# Angular_Position_Feedback.net
KiCad netlist of a schematic drawn in Altium Designer
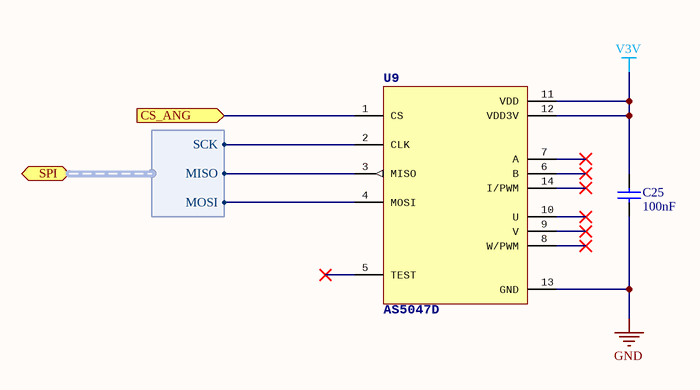
[diagram p0: Angular_Position_Feedback.SchDoc]

(export (version "E")
  (design (tool "Eeschema 10.0.6"))
  (components
    (comp (ref "C25")
      (value "100nF")
      (footprint "CAPC1608X06N (0603)")
      (description "Capacitor (Semiconductor SIM Model)")
      (fields (field (name "Comment") "Cap Semi") (field (name "PUBLISHER") "Altium Limited"))
      (libsource (lib "miStepper_SchematicLib") (part "Cap Semi"))
    )
    (comp (ref "U9")
      (value "AS5047D")
      (footprint "TSSOP14")
      (libsource (lib "miStepper_SchematicLib") (part "AS5047D"))
    )
  )
  (nets
    (net (code "2") (name "/CS_ANG") (class "Default")
      (node (ref "U9") (pin "1") (pinfunction "CS_1") (pintype "passive"))
    )
    (net (code "3") (name "/MISO") (class "Default")
      (node (ref "U9") (pin "3") (pinfunction "MISO_3") (pintype "output"))
    )
    (net (code "4") (name "/MOSI") (class "Default")
      (node (ref "U9") (pin "4") (pinfunction "MOSI_4") (pintype "passive"))
    )
    (net (code "5") (name "/SCK") (class "Default")
      (node (ref "U9") (pin "2") (pinfunction "CLK_2") (pintype "passive"))
    )
    (net (code "7") (name "GND") (class "Default")
      (node (ref "C25") (pin "1") (pinfunction "1_1") (pintype "passive"))
      (node (ref "U9") (pin "13") (pinfunction "GND_13") (pintype "power_in"))
    )
    (net (code "8") (name "V3V") (class "Default")
      (node (ref "C25") (pin "2") (pinfunction "2_2") (pintype "passive"))
      (node (ref "U9") (pin "11") (pinfunction "VDD_11") (pintype "power_in"))
      (node (ref "U9") (pin "12") (pinfunction "VDD3V_12") (pintype "power_in"))
    )
    (net (code "9") (name "unconnected-(U9-A-Pad7)") (class "Default")
      (node (ref "U9") (pin "7") (pinfunction "A_7") (pintype "passive+no_connect"))
    )
    (net (code "10") (name "unconnected-(U9-B-Pad6)") (class "Default")
      (node (ref "U9") (pin "6") (pinfunction "B_6") (pintype "passive+no_connect"))
    )
    (net (code "11") (name "unconnected-(U9-I{slash}PWM-Pad14)") (class "Default")
      (node (ref "U9") (pin "14") (pinfunction "I/PWM_14") (pintype "passive+no_connect"))
    )
    (net (code "12") (name "unconnected-(U9-TEST-Pad5)") (class "Default")
      (node (ref "U9") (pin "5") (pinfunction "TEST_5") (pintype "passive+no_connect"))
    )
    (net (code "13") (name "unconnected-(U9-U-Pad10)") (class "Default")
      (node (ref "U9") (pin "10") (pinfunction "U_10") (pintype "passive+no_connect"))
    )
    (net (code "14") (name "unconnected-(U9-V-Pad9)") (class "Default")
      (node (ref "U9") (pin "9") (pinfunction "V_9") (pintype "passive+no_connect"))
    )
    (net (code "15") (name "unconnected-(U9-W{slash}PWM-Pad8)") (class "Default")
      (node (ref "U9") (pin "8") (pinfunction "W/PWM_8") (pintype "passive+no_connect"))
    )
  )
)
